# MPPTcharger.net
KiCad netlist of a schematic drawn in Altium Designer
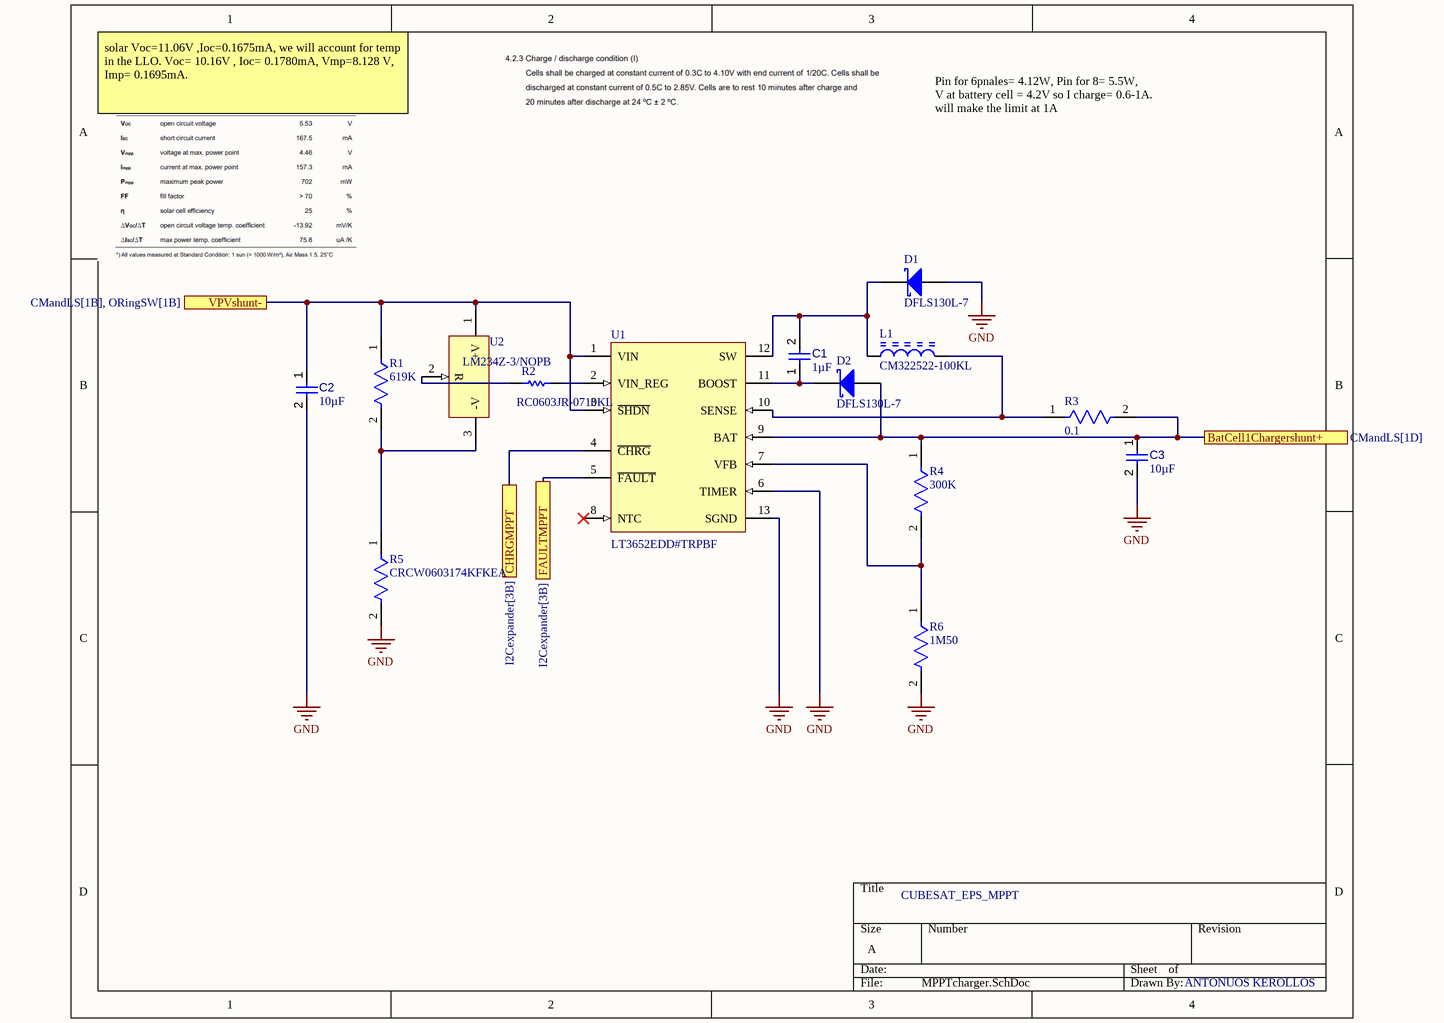
[diagram p0: MPPTcharger.SchDoc]

(export (version "E")
  (design (tool "Eeschema 10.0.6"))
  (components
    (comp (ref "C1")
      (value "1µF")
      (footprint "CAPC0402(1005)60_L")
      (description "Chip Capacitor, 1µF +/-20%, 10V, 0402, Thickness 0.6 mm")
      (fields (field (name "TOLERANCE") "10%") (field (name "Comment") "Capacitor 1µF +/-20% 10V 0402"))
      (libsource (lib "ANTONUOS KEROLLOS") (part "CAP-NP-2"))
    )
    (comp (ref "C2")
      (value "10µF")
      (footprint "CAPC0402(1005)60_L")
      (description "Chip Capacitor, 10µF +/-40%, 6.3V, 0402, Thickness 0.6 mm")
      (fields (field (name "TOLERANCE") "10%") (field (name "Comment") "Capacitor 10µF +/-40% 6.3V 0402"))
      (libsource (lib "ANTONUOS KEROLLOS") (part "CAP-NP-2"))
    )
    (comp (ref "C3")
      (value "10µF")
      (footprint "CAPC0402(1005)60_L")
      (description "Chip Capacitor, 10µF +/-40%, 6.3V, 0402, Thickness 0.6 mm")
      (fields (field (name "TOLERANCE") "10%") (field (name "Comment") "Capacitor 10µF +/-40% 6.3V 0402"))
      (libsource (lib "ANTONUOS KEROLLOS") (part "CAP-NP-2"))
    )
    (comp (ref "D1")
      (value "DFLS130L-7")
      (footprint "DIOD-POWERDI123-2_A_V")
      (description "Schottky Barrier Rectifier, 30 V, 1 A, -40 to 125 degC, 2-Pin SMD, RoHS, Tape and Reel")
      (fields (field (name "MANUFACTURER") "Diodes Inc"))
      (libsource (lib "Altium Content Vault") (part "DSKY-AK-2"))
    )
    (comp (ref "D2")
      (value "DFLS130L-7")
      (footprint "DIOD-POWERDI123-2_A_V")
      (description "Schottky Barrier Rectifier, 30 V, 1 A, -40 to 125 degC, 2-Pin SMD, RoHS, Tape and Reel")
      (fields (field (name "MANUFACTURER") "Diodes Inc"))
      (libsource (lib "Altium Content Vault") (part "DSKY-AK-2"))
    )
    (comp (ref "L1")
      (value "CM322522-100KL")
      (footprint "BOUR-CM322522_V")
      (description "Chip Inductor\r\n, 10 uH, +/- 10%, -40 to 125 degC, 1210 (3225 Metric), RoHS, Tape and Reel")
      (libsource (lib "Altium Content Vault") (part "BOUR-IND-2A"))
    )
    (comp (ref "R1")
      (value "619K")
      (footprint "FP-CRCW0805-e3-IPC_C")
      (description "RES Thick Film, 619kΩ, 1%, 0.125W, 100ppm/°C, 0805")
      (fields (field (name "TOLERANCE") "1%"))
      (libsource (lib "Altium Content Vault") (part "1029c3af85768c4190bb7ad29bc67b5"))
    )
    (comp (ref "R2")
      (value "RC0603JR-0710KL")
      (footprint "RESC1608X55X25ML10T15")
      (description "Resistor, 10 KOhm, +/- 5%, 100 mW, -55 to 155 degC, 0603 (1608 Metric), RoHS, Tape and Reel")
      (fields (field (name "MANUFACTURER") "Yageo") (field (name "TOLERANCE") "5%"))
      (libsource (lib "Altium Content Vault") (part "RES-2"))
    )
    (comp (ref "R3")
      (value "0.1")
      (footprint "FP-ERJ8BW-IPC_A")
      (description "RES 0.1 OHM 1% 1W 1206")
      (fields (field (name "TOLERANCE") "1%"))
      (libsource (lib "Altium Content Vault") (part "1029c3af85768c4190bb7ad29bc67b5"))
    )
    (comp (ref "R4")
      (value "300K")
      (footprint "FP-CRCW0402-e3-IPC_C")
      (description "RES Thick Film, 300kΩ, 1%, 0.063W, 100ppm/°C, 0402")
      (fields (field (name "TOLERANCE") "1%"))
      (libsource (lib "Altium Content Vault") (part "1029c3af85768c4190bb7ad29bc67b5"))
    )
    (comp (ref "R5")
      (value "CRCW0603174KFKEA")
      (footprint "FP-CRCW0603-e3-IPC_B")
      (description "RES Thick Film, 174kΩ, 1%, 0.1W, 100ppm/°C, 0603")
      (fields (field (name "TOLERANCE") "1%"))
      (libsource (lib "Altium Content Vault") (part "1029c3af85768c4190bb7ad29bc67b5"))
    )
    (comp (ref "R6")
      (value "1M50")
      (footprint "FP-CRCW0402-e3-IPC_C")
      (description "RES Thick Film, 1.5MΩ, 1%, 0.063W, 100ppm/°C, 0402")
      (fields (field (name "TOLERANCE") "1%"))
      (libsource (lib "Altium Content Vault") (part "1029c3af85768c4190bb7ad29bc67b5"))
    )
    (comp (ref "U1")
      (value "LT3652EDD#TRPBF")
      (footprint "LT-DD-12_V")
      (fields (field (name "MANUFACTURER") "Linear Technology"))
      (libsource (lib "Altium Content Vault") (part "LT-LT3652XX-12"))
    )
    (comp (ref "U2")
      (value "LM234Z-3/NOPB")
      (footprint "LP0003A")
      (description "3-Terminal Adjustable Current Source, 3-pin TO-92, Pb-Free")
      (fields (field (name "MANUFACTURER") "Texas Instruments"))
      (libsource (lib "Altium Content Vault") (part "PM-ISRC-LM234Z-3"))
    )
  )
  (nets
    (net (code "1") (name "/BatCell1Chargershunt+") (class "Default")
      (node (ref "C3") (pin "1") (pinfunction "1_1") (pintype "passive"))
      (node (ref "D2") (pin "1") (pinfunction "A_1") (pintype "passive"))
      (node (ref "R3") (pin "2") (pinfunction "2_2") (pintype "passive"))
      (node (ref "R4") (pin "1") (pinfunction "1_1") (pintype "passive"))
      (node (ref "U1") (pin "9") (pinfunction "BAT_9") (pintype "input"))
    )
    (net (code "2") (name "/CHRGMPPT") (class "Default")
      (node (ref "U1") (pin "4") (pinfunction "~{CHRG}_4") (pintype "tri_state"))
    )
    (net (code "3") (name "/FAULTMPPT") (class "Default")
      (node (ref "U1") (pin "5") (pinfunction "~{FAULT}_5") (pintype "tri_state"))
    )
    (net (code "4") (name "/VPVshunt-") (class "Default")
      (node (ref "C2") (pin "1") (pinfunction "1_1") (pintype "passive"))
      (node (ref "R1") (pin "1") (pinfunction "1_1") (pintype "passive"))
      (node (ref "U1") (pin "1") (pinfunction "VIN_1") (pintype "power_in"))
      (node (ref "U1") (pin "3") (pinfunction "~{SHDN}_3") (pintype "input"))
      (node (ref "U2") (pin "1") (pinfunction "+V_1") (pintype "passive"))
    )
    (net (code "5") (name "GND") (class "Default")
      (node (ref "C2") (pin "2") (pinfunction "2_2") (pintype "passive"))
      (node (ref "C3") (pin "2") (pinfunction "2_2") (pintype "passive"))
      (node (ref "D1") (pin "1") (pinfunction "A_1") (pintype "passive"))
      (node (ref "R5") (pin "2") (pinfunction "2_2") (pintype "passive"))
      (node (ref "R6") (pin "2") (pinfunction "2_2") (pintype "passive"))
      (node (ref "U1") (pin "13") (pinfunction "SGND_13") (pintype "power_in"))
      (node (ref "U1") (pin "6") (pinfunction "TIMER_6") (pintype "input"))
    )
    (net (code "6") (name "Net-(D1-K)") (class "Default")
      (node (ref "C1") (pin "2") (pinfunction "2_2") (pintype "passive"))
      (node (ref "D1") (pin "2") (pinfunction "K_2") (pintype "passive"))
      (node (ref "L1") (pin "1") (pinfunction "1_1") (pintype "passive"))
      (node (ref "U1") (pin "12") (pinfunction "SW_12") (pintype "power_in"))
    )
    (net (code "7") (name "Net-(D2-K)") (class "Default")
      (node (ref "C1") (pin "1") (pinfunction "1_1") (pintype "passive"))
      (node (ref "D2") (pin "2") (pinfunction "K_2") (pintype "passive"))
      (node (ref "U1") (pin "11") (pinfunction "BOOST_11") (pintype "power_in"))
    )
    (net (code "8") (name "Net-(U1-SENSE)") (class "Default")
      (node (ref "L1") (pin "2") (pinfunction "2_2") (pintype "passive"))
      (node (ref "R3") (pin "1") (pinfunction "1_1") (pintype "passive"))
      (node (ref "U1") (pin "10") (pinfunction "SENSE_10") (pintype "input"))
    )
    (net (code "9") (name "Net-(U1-VFB)") (class "Default")
      (node (ref "R4") (pin "2") (pinfunction "2_2") (pintype "passive"))
      (node (ref "R6") (pin "1") (pinfunction "1_1") (pintype "passive"))
      (node (ref "U1") (pin "7") (pinfunction "VFB_7") (pintype "input"))
    )
    (net (code "10") (name "Net-(U1-VIN_REG)") (class "Default")
      (node (ref "R2") (pin "1") (pinfunction "1_1") (pintype "passive"))
      (node (ref "U1") (pin "2") (pinfunction "VIN_REG_2") (pintype "input"))
    )
    (net (code "11") (name "Net-(U2--V)") (class "Default")
      (node (ref "R1") (pin "2") (pinfunction "2_2") (pintype "passive"))
      (node (ref "R5") (pin "1") (pinfunction "1_1") (pintype "passive"))
      (node (ref "U2") (pin "3") (pinfunction "-V_3") (pintype "passive"))
    )
    (net (code "12") (name "Net-(U2-R)") (class "Default")
      (node (ref "R2") (pin "2") (pinfunction "2_2") (pintype "passive"))
      (node (ref "U2") (pin "2") (pinfunction "R_2") (pintype "input"))
    )
    (net (code "13") (name "unconnected-(U1-NTC-Pad8)") (class "Default")
      (node (ref "U1") (pin "8") (pinfunction "NTC_8") (pintype "input+no_connect"))
    )
  )
)
